# ESP-OLED.net
KiCad netlist of a schematic drawn in Altium Designer
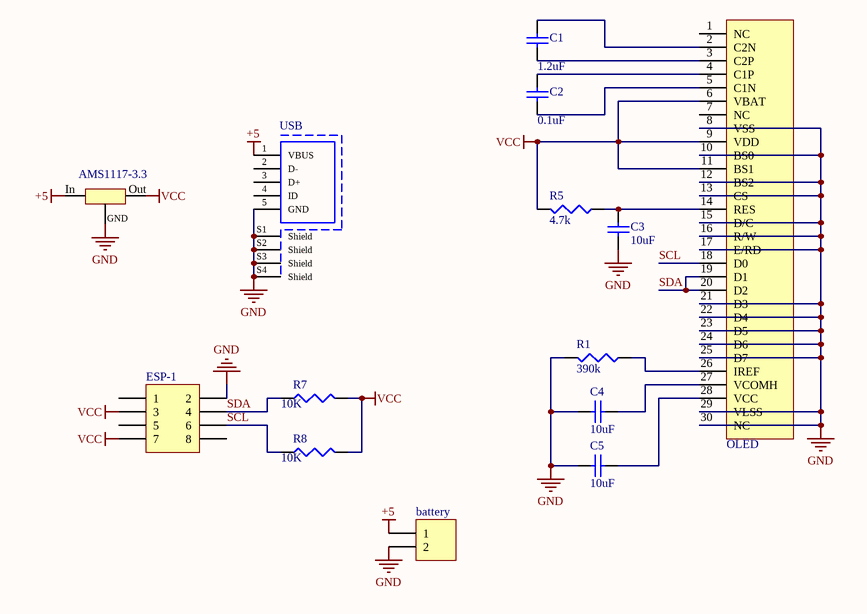
[diagram p0: ESP-OLED.SchDoc]

(export (version "E")
  (design (tool "Eeschema 10.0.6"))
  (components
    (comp (ref "battery")
      (value "Header 2")
      (footprint "HDR1X2")
      (description "Header, 2-Pin")
      (fields (field (name "PUBLISHER") "Altium Limited"))
      (libsource (lib "Miscellaneous Connectors") (part "Header 2"))
    )
    (comp (ref "C1")
      (value "1.2uF")
      (footprint "1608[0603]")
      (description "Capacitor (Semiconductor SIM Model)")
      (fields (field (name "Comment") "Cap Semi") (field (name "PUBLISHER") "Altium Limited"))
      (libsource (lib "Miscellaneous Devices") (part "Cap Semi"))
    )
    (comp (ref "C2")
      (value "0.1uF")
      (footprint "1608[0603]")
      (description "Capacitor (Semiconductor SIM Model)")
      (fields (field (name "Comment") "Cap Semi") (field (name "PUBLISHER") "Altium Limited"))
      (libsource (lib "Miscellaneous Devices") (part "Cap Semi"))
    )
    (comp (ref "C3")
      (value "10uF")
      (footprint "1608[0603]")
      (description "Capacitor (Semiconductor SIM Model)")
      (fields (field (name "Comment") "Cap Semi") (field (name "PUBLISHER") "Altium Limited"))
      (libsource (lib "Miscellaneous Devices") (part "Cap Semi"))
    )
    (comp (ref "C4")
      (value "10uF")
      (footprint "1608[0603]")
      (description "Capacitor (Semiconductor SIM Model)")
      (fields (field (name "Comment") "Cap Semi") (field (name "PUBLISHER") "Altium Limited"))
      (libsource (lib "Miscellaneous Devices") (part "Cap Semi"))
    )
    (comp (ref "C5")
      (value "10uF")
      (footprint "1608[0603]")
      (description "Capacitor (Semiconductor SIM Model)")
      (fields (field (name "Comment") "Cap Semi") (field (name "PUBLISHER") "Altium Limited"))
      (libsource (lib "Miscellaneous Devices") (part "Cap Semi"))
    )
    (comp (ref "ESP-1")
      (value "Header 4X2")
      (footprint "ESP-01")
      (description "Header, 4-Pin, Dual row")
      (fields (field (name "PUBLISHER") "Altium Limited"))
      (libsource (lib "Miscellaneous Connectors") (part "Header 4X2"))
    )
    (comp (ref "OLED") (value "OLED") (footprint "oled0.96_no3d") (libsource (lib "arad") (part "OLED0.96")))
    (comp (ref "R1")
      (value "390k")
      (footprint "J1-0603")
      (description "Resistor")
      (fields (field (name "Comment") "Res3") (field (name "PUBLISHER") "Altium Limited"))
      (libsource (lib "Miscellaneous Devices") (part "Res3"))
    )
    (comp (ref "R5")
      (value "4.7k")
      (footprint "J1-0603")
      (description "Resistor")
      (fields (field (name "Comment") "Res3") (field (name "PUBLISHER") "Altium Limited"))
      (libsource (lib "Miscellaneous Devices") (part "Res3"))
    )
    (comp (ref "R7")
      (value "10K")
      (footprint "J1-0603")
      (description "Resistor")
      (fields (field (name "Comment") "Res3") (field (name "PUBLISHER") "Altium Limited"))
      (libsource (lib "Miscellaneous Devices") (part "Res3"))
    )
    (comp (ref "R8")
      (value "10K")
      (footprint "J1-0603")
      (description "Resistor")
      (fields (field (name "Comment") "Res3") (field (name "PUBLISHER") "Altium Limited"))
      (libsource (lib "Miscellaneous Devices") (part "Res3"))
    )
    (comp (ref "reg")
      (value "AMS1117-3.3")
      (footprint "SOT223")
      (libsource (lib "Diverse") (part "AMS1117-3.3"))
    )
    (comp (ref "USB")
      (value "Micro USB 2.0 Type B Receptacle")
      (footprint "629105150521")
      (description "Micro USB 2.0 Type B, Receptacle, Horizontal, SMT, with Pegs")
      (fields (field (name "PART NUMBER") "629105150521") (field (name "PUBLISHER") "Wurth Elektronik"))
      (libsource (lib "arad") (part "629105150521"))
    )
  )
  (nets
    (net (code "1") (name "+5") (class "Default")
      (node (ref "USB") (pin "1") (pinfunction "VBUS_1") (pintype "passive"))
      (node (ref "battery") (pin "1") (pinfunction "1_1") (pintype "passive"))
      (node (ref "reg") (pin "3") (pinfunction "3_3") (pintype "passive"))
    )
    (net (code "2") (name "/SCL") (class "Default")
      (node (ref "ESP-1") (pin "6") (pinfunction "6_6") (pintype "passive"))
      (node (ref "OLED") (pin "18") (pinfunction "D0_18") (pintype "passive"))
      (node (ref "R8") (pin "1") (pinfunction "1_1") (pintype "passive"))
    )
    (net (code "3") (name "/SDA") (class "Default")
      (node (ref "ESP-1") (pin "4") (pinfunction "4_4") (pintype "passive"))
      (node (ref "OLED") (pin "19") (pinfunction "D1_19") (pintype "passive"))
      (node (ref "OLED") (pin "20") (pinfunction "D2_20") (pintype "passive"))
      (node (ref "R7") (pin "1") (pinfunction "1_1") (pintype "passive"))
    )
    (net (code "4") (name "GND") (class "Default")
      (node (ref "C3") (pin "1") (pinfunction "1_1") (pintype "passive"))
      (node (ref "C4") (pin "2") (pinfunction "2_2") (pintype "passive"))
      (node (ref "C5") (pin "2") (pinfunction "2_2") (pintype "passive"))
      (node (ref "ESP-1") (pin "2") (pinfunction "2_2") (pintype "passive"))
      (node (ref "OLED") (pin "10") (pinfunction "BS0_10") (pintype "passive"))
      (node (ref "OLED") (pin "12") (pinfunction "BS2_12") (pintype "passive"))
      (node (ref "OLED") (pin "13") (pinfunction "CS_13") (pintype "passive"))
      (node (ref "OLED") (pin "15") (pinfunction "D/C_15") (pintype "passive"))
      (node (ref "OLED") (pin "16") (pinfunction "R/W_16") (pintype "passive"))
      (node (ref "OLED") (pin "17") (pinfunction "E/RD_17") (pintype "passive"))
      (node (ref "OLED") (pin "21") (pinfunction "D3_21") (pintype "passive"))
      (node (ref "OLED") (pin "22") (pinfunction "D4_22") (pintype "passive"))
      (node (ref "OLED") (pin "23") (pinfunction "D5_23") (pintype "passive"))
      (node (ref "OLED") (pin "24") (pinfunction "D6_24") (pintype "passive"))
      (node (ref "OLED") (pin "25") (pinfunction "D7_25") (pintype "passive"))
      (node (ref "OLED") (pin "29") (pinfunction "VLSS_29") (pintype "passive"))
      (node (ref "OLED") (pin "30") (pinfunction "NC_30") (pintype "passive"))
      (node (ref "OLED") (pin "8") (pinfunction "VSS_8") (pintype "passive"))
      (node (ref "R1") (pin "2") (pinfunction "2_2") (pintype "passive"))
      (node (ref "USB") (pin "5") (pinfunction "GND_5") (pintype "passive"))
      (node (ref "USB") (pin "S1") (pinfunction "Shield_S1") (pintype "passive"))
      (node (ref "USB") (pin "S2") (pinfunction "Shield_S2") (pintype "passive"))
      (node (ref "USB") (pin "S3") (pinfunction "Shield_S3") (pintype "passive"))
      (node (ref "USB") (pin "S4") (pinfunction "Shield_S4") (pintype "passive"))
      (node (ref "battery") (pin "2") (pinfunction "2_2") (pintype "passive"))
      (node (ref "reg") (pin "1") (pinfunction "1_1") (pintype "passive"))
    )
    (net (code "5") (name "Net-(OLED-C1N)") (class "Default")
      (node (ref "C2") (pin "1") (pinfunction "1_1") (pintype "passive"))
      (node (ref "OLED") (pin "5") (pinfunction "C1N_5") (pintype "passive"))
    )
    (net (code "6") (name "Net-(OLED-C1P)") (class "Default")
      (node (ref "C2") (pin "2") (pinfunction "2_2") (pintype "passive"))
      (node (ref "OLED") (pin "4") (pinfunction "C1P_4") (pintype "passive"))
    )
    (net (code "7") (name "Net-(OLED-C2N)") (class "Default")
      (node (ref "C1") (pin "2") (pinfunction "2_2") (pintype "passive"))
      (node (ref "OLED") (pin "2") (pinfunction "C2N_2") (pintype "passive"))
    )
    (net (code "8") (name "Net-(OLED-C2P)") (class "Default")
      (node (ref "C1") (pin "1") (pinfunction "1_1") (pintype "passive"))
      (node (ref "OLED") (pin "3") (pinfunction "C2P_3") (pintype "passive"))
    )
    (net (code "9") (name "Net-(OLED-IREF)") (class "Default")
      (node (ref "OLED") (pin "26") (pinfunction "IREF_26") (pintype "passive"))
      (node (ref "R1") (pin "1") (pinfunction "1_1") (pintype "passive"))
    )
    (net (code "10") (name "Net-(OLED-RES)") (class "Default")
      (node (ref "C3") (pin "2") (pinfunction "2_2") (pintype "passive"))
      (node (ref "OLED") (pin "14") (pinfunction "RES_14") (pintype "passive"))
      (node (ref "R5") (pin "1") (pinfunction "1_1") (pintype "passive"))
    )
    (net (code "11") (name "Net-(OLED-VCC)") (class "Default")
      (node (ref "C5") (pin "1") (pinfunction "1_1") (pintype "passive"))
      (node (ref "OLED") (pin "28") (pinfunction "VCC_28") (pintype "passive"))
    )
    (net (code "12") (name "Net-(OLED-VCOMH)") (class "Default")
      (node (ref "C4") (pin "1") (pinfunction "1_1") (pintype "passive"))
      (node (ref "OLED") (pin "27") (pinfunction "VCOMH_27") (pintype "passive"))
    )
    (net (code "13") (name "VCC") (class "Default")
      (node (ref "ESP-1") (pin "3") (pinfunction "3_3") (pintype "passive"))
      (node (ref "ESP-1") (pin "7") (pinfunction "7_7") (pintype "passive"))
      (node (ref "OLED") (pin "11") (pinfunction "BS1_11") (pintype "passive"))
      (node (ref "OLED") (pin "6") (pinfunction "VBAT_6") (pintype "passive"))
      (node (ref "OLED") (pin "9") (pinfunction "VDD_9") (pintype "passive"))
      (node (ref "R5") (pin "2") (pinfunction "2_2") (pintype "passive"))
      (node (ref "R7") (pin "2") (pinfunction "2_2") (pintype "passive"))
      (node (ref "R8") (pin "2") (pinfunction "2_2") (pintype "passive"))
      (node (ref "reg") (pin "2") (pinfunction "2_2") (pintype "passive"))
    )
    (net (code "14") (name "unconnected-(ESP-1-Pad1)") (class "Default")
      (node (ref "ESP-1") (pin "1") (pinfunction "1_1") (pintype "passive"))
    )
    (net (code "15") (name "unconnected-(ESP-1-Pad5)") (class "Default")
      (node (ref "ESP-1") (pin "5") (pinfunction "5_5") (pintype "passive"))
    )
    (net (code "16") (name "unconnected-(ESP-1-Pad8)") (class "Default")
      (node (ref "ESP-1") (pin "8") (pinfunction "8_8") (pintype "passive"))
    )
    (net (code "17") (name "unconnected-(OLED-NC-Pad1)") (class "Default")
      (node (ref "OLED") (pin "1") (pinfunction "NC_1") (pintype "passive"))
    )
    (net (code "18") (name "unconnected-(OLED-NC-Pad7)") (class "Default")
      (node (ref "OLED") (pin "7") (pinfunction "NC_7") (pintype "passive"))
    )
    (net (code "19") (name "unconnected-(USB-D+-Pad3)") (class "Default")
      (node (ref "USB") (pin "3") (pinfunction "D+_3") (pintype "passive"))
    )
    (net (code "20") (name "unconnected-(USB-D--Pad2)") (class "Default")
      (node (ref "USB") (pin "2") (pinfunction "D-_2") (pintype "passive"))
    )
    (net (code "21") (name "unconnected-(USB-ID-Pad4)") (class "Default")
      (node (ref "USB") (pin "4") (pinfunction "ID_4") (pintype "passive"))
    )
  )
)
